# Top.net
KiCad netlist of a schematic drawn in Altium Designer
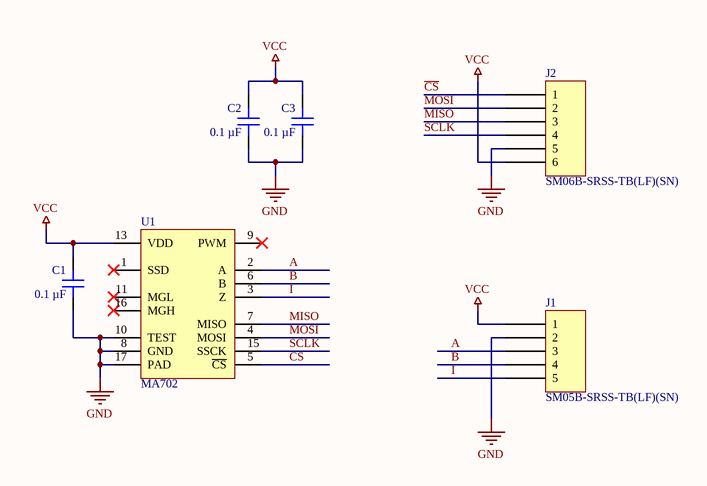
[diagram p0: Top.SchDoc]

(export (version "E")
  (design (tool "Eeschema 10.0.6"))
  (components
    (comp (ref "C1")
      (value "0.1 µF")
      (footprint "CAP 0402_1005")
      (description "CAP CER 0.1UF 25V X7R 0402")
      (fields (field (name "PART NUMBER") "C0402C104K3RAC7867") (field (name "MANUFACTURER") "KEMET"))
      (libsource (lib "Celestial Altium Library - altium_library") (part "Capacitor"))
    )
    (comp (ref "C2")
      (value "0.1 µF")
      (footprint "CAP 0402_1005")
      (description "CAP CER 0.1UF 25V X7R 0402")
      (fields (field (name "PART NUMBER") "C0402C104K3RAC7867") (field (name "MANUFACTURER") "KEMET"))
      (libsource (lib "Celestial Altium Library - altium_library") (part "Capacitor"))
    )
    (comp (ref "C3")
      (value "0.1 µF")
      (footprint "CAP 0402_1005")
      (description "CAP CER 0.1UF 25V X7R 0402")
      (fields (field (name "PART NUMBER") "C0402C104K3RAC7867") (field (name "MANUFACTURER") "KEMET"))
      (libsource (lib "Celestial Altium Library - altium_library") (part "Capacitor"))
    )
    (comp (ref "J1")
      (value "SM05B-SRSS-TB(LF)(SN)")
      (footprint "JST SM05B-SRSS-TB")
      (description "CONN HEADER SMD R/A 5POS 1MM")
      (fields (field (name "MANUFACTURER") "JST Sales America Inc."))
      (libsource (lib "Celestial Altium Library - altium_library") (part "5 Pin"))
    )
    (comp (ref "J2")
      (value "SM06B-SRSS-TB(LF)(SN)")
      (footprint "JST SM06B-SRSS-TB")
      (description "CONN HEADER SMD R/A 6POS 1MM")
      (fields (field (name "MANUFACTURER") "JST Sales America Inc."))
      (libsource (lib "Celestial Altium Library - altium_library") (part "6 Pin"))
    )
    (comp (ref "U1")
      (value "MA702")
      (footprint "IC_MA702GQ-Z")
      (description "Hall effect encoder")
      (libsource (lib "IC") (part "MA702"))
    )
  )
  (nets
    (net (code "1") (name "/A") (class "Default")
      (node (ref "J1") (pin "3") (pinfunction "3_3") (pintype "passive"))
      (node (ref "U1") (pin "2") (pinfunction "A_2") (pintype "passive"))
    )
    (net (code "2") (name "/B") (class "Default")
      (node (ref "J1") (pin "4") (pinfunction "4_4") (pintype "passive"))
      (node (ref "U1") (pin "6") (pinfunction "B_6") (pintype "passive"))
    )
    (net (code "3") (name "/I") (class "Default")
      (node (ref "J1") (pin "5") (pinfunction "5_5") (pintype "passive"))
      (node (ref "U1") (pin "3") (pinfunction "Z_3") (pintype "passive"))
    )
    (net (code "4") (name "/MISO") (class "Default")
      (node (ref "J2") (pin "3") (pinfunction "3_3") (pintype "passive"))
      (node (ref "U1") (pin "7") (pinfunction "MISO_7") (pintype "passive"))
    )
    (net (code "5") (name "/MOSI") (class "Default")
      (node (ref "J2") (pin "2") (pinfunction "2_2") (pintype "passive"))
      (node (ref "U1") (pin "4") (pinfunction "MOSI_4") (pintype "passive"))
    )
    (net (code "6") (name "/SCLK") (class "Default")
      (node (ref "J2") (pin "4") (pinfunction "4_4") (pintype "passive"))
      (node (ref "U1") (pin "15") (pinfunction "SSCK_15") (pintype "passive"))
    )
    (net (code "7") (name "/~{CS}") (class "Default")
      (node (ref "J2") (pin "1") (pinfunction "1_1") (pintype "passive"))
      (node (ref "U1") (pin "5") (pinfunction "~{CS}_5") (pintype "passive"))
    )
    (net (code "8") (name "GND") (class "Default")
      (node (ref "C1") (pin "2") (pinfunction "2_2") (pintype "passive"))
      (node (ref "C2") (pin "2") (pinfunction "2_2") (pintype "passive"))
      (node (ref "C3") (pin "2") (pinfunction "2_2") (pintype "passive"))
      (node (ref "J1") (pin "2") (pinfunction "2_2") (pintype "passive"))
      (node (ref "J2") (pin "5") (pinfunction "5_5") (pintype "passive"))
      (node (ref "U1") (pin "10") (pinfunction "TEST_10") (pintype "passive"))
      (node (ref "U1") (pin "17") (pinfunction "PAD_17") (pintype "passive"))
      (node (ref "U1") (pin "8") (pinfunction "GND_8") (pintype "passive"))
    )
    (net (code "9") (name "VCC") (class "Default")
      (node (ref "C1") (pin "1") (pinfunction "1_1") (pintype "passive"))
      (node (ref "C2") (pin "1") (pinfunction "1_1") (pintype "passive"))
      (node (ref "C3") (pin "1") (pinfunction "1_1") (pintype "passive"))
      (node (ref "J1") (pin "1") (pinfunction "1_1") (pintype "passive"))
      (node (ref "J2") (pin "6") (pinfunction "6_6") (pintype "passive"))
      (node (ref "U1") (pin "13") (pinfunction "VDD_13") (pintype "passive"))
    )
    (net (code "10") (name "unconnected-(U1-MGH-Pad16)") (class "Default")
      (node (ref "U1") (pin "16") (pinfunction "MGH_16") (pintype "passive+no_connect"))
    )
    (net (code "11") (name "unconnected-(U1-MGL-Pad11)") (class "Default")
      (node (ref "U1") (pin "11") (pinfunction "MGL_11") (pintype "passive+no_connect"))
    )
    (net (code "12") (name "unconnected-(U1-PWM-Pad9)") (class "Default")
      (node (ref "U1") (pin "9") (pinfunction "PWM_9") (pintype "passive+no_connect"))
    )
    (net (code "13") (name "unconnected-(U1-SSD-Pad1)") (class "Default")
      (node (ref "U1") (pin "1") (pinfunction "SSD_1") (pintype "passive+no_connect"))
    )
  )
)
